# relays.net
KiCad netlist of a schematic drawn in Altium Designer
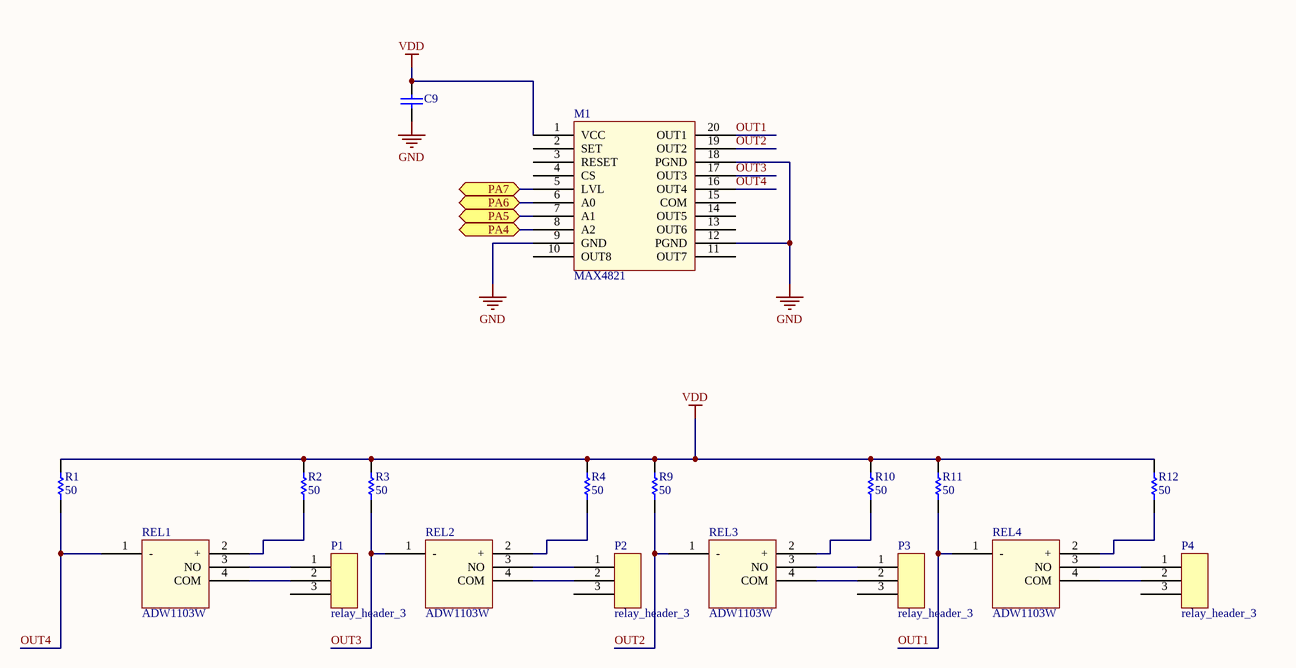
[diagram p0: relays.SchDoc]

(export (version "E")
  (design (tool "Eeschema 10.0.6"))
  (components
    (comp (ref "C9")
      (value "Cap Semi")
      (footprint "1608[0603]")
      (description "Capacitor (Semiconductor SIM Model)")
      (fields (field (name "MANUFACTURER") "TDK") (field (name "PUBLISHER") "Altium Limited"))
      (libsource (lib "Miscellaneous Devices") (part "Cap Semi"))
    )
    (comp (ref "M1")
      (value "MAX4821")
      (footprint "MAX4821")
      (fields (field (name "MANUFACTURER") "Maxim Integrated"))
      (libsource (lib "seeds") (part "MAX4821"))
    )
    (comp (ref "P1")
      (value "relay_header_3")
      (footprint "ac_header_3")
      (fields (field (name "MANUFACTURER") "On Shore Technology"))
      (libsource (lib "seeds") (part "relay_header_3"))
    )
    (comp (ref "P2")
      (value "relay_header_3")
      (footprint "ac_header_3")
      (fields (field (name "MANUFACTURER") "On Shore Technology"))
      (libsource (lib "seeds") (part "relay_header_3"))
    )
    (comp (ref "P3")
      (value "relay_header_3")
      (footprint "ac_header_3")
      (fields (field (name "MANUFACTURER") "On Shore Technology"))
      (libsource (lib "seeds") (part "relay_header_3"))
    )
    (comp (ref "P4")
      (value "relay_header_3")
      (footprint "ac_header_3")
      (fields (field (name "MANUFACTURER") "On Shore Technology"))
      (libsource (lib "seeds") (part "relay_header_3"))
    )
    (comp (ref "R1")
      (value "50")
      (footprint "0603R")
      (description "Resistor")
      (fields (field (name "MANUFACTURER") "Vishay Dale") (field (name "PUBLISHER") "Altium Limited"))
      (libsource (lib "MB1136") (part "Res1"))
    )
    (comp (ref "R2")
      (value "50")
      (footprint "0603R")
      (description "Resistor")
      (fields (field (name "MANUFACTURER") "Vishay Dale") (field (name "PUBLISHER") "Altium Limited"))
      (libsource (lib "MB1136") (part "Res1"))
    )
    (comp (ref "R3")
      (value "50")
      (footprint "0603R")
      (description "Resistor")
      (fields (field (name "MANUFACTURER") "Vishay Dale") (field (name "PUBLISHER") "Altium Limited"))
      (libsource (lib "MB1136") (part "Res1"))
    )
    (comp (ref "R4")
      (value "50")
      (footprint "0603R")
      (description "Resistor")
      (fields (field (name "MANUFACTURER") "Vishay Dale") (field (name "PUBLISHER") "Altium Limited"))
      (libsource (lib "MB1136") (part "Res1"))
    )
    (comp (ref "R9")
      (value "50")
      (footprint "0603R")
      (description "Resistor")
      (fields (field (name "MANUFACTURER") "Vishay Dale") (field (name "PUBLISHER") "Altium Limited"))
      (libsource (lib "MB1136") (part "Res1"))
    )
    (comp (ref "R10")
      (value "50")
      (footprint "0603R")
      (description "Resistor")
      (fields (field (name "MANUFACTURER") "Vishay Dale") (field (name "PUBLISHER") "Altium Limited"))
      (libsource (lib "MB1136") (part "Res1"))
    )
    (comp (ref "R11")
      (value "50")
      (footprint "0603R")
      (description "Resistor")
      (fields (field (name "MANUFACTURER") "Vishay Dale") (field (name "PUBLISHER") "Altium Limited"))
      (libsource (lib "MB1136") (part "Res1"))
    )
    (comp (ref "R12")
      (value "50")
      (footprint "0603R")
      (description "Resistor")
      (fields (field (name "MANUFACTURER") "Vishay Dale") (field (name "PUBLISHER") "Altium Limited"))
      (libsource (lib "MB1136") (part "Res1"))
    )
    (comp (ref "REL1")
      (value "ADW1103W")
      (footprint "ADW1103W")
      (fields (field (name "MANUFACTURER") "Panasonic"))
      (libsource (lib "seeds") (part "ADW1103W"))
    )
    (comp (ref "REL2")
      (value "ADW1103W")
      (footprint "ADW1103W")
      (fields (field (name "MANUFACTURER") "Panasonic"))
      (libsource (lib "seeds") (part "ADW1103W"))
    )
    (comp (ref "REL3")
      (value "ADW1103W")
      (footprint "ADW1103W")
      (fields (field (name "MANUFACTURER") "Panasonic"))
      (libsource (lib "seeds") (part "ADW1103W"))
    )
    (comp (ref "REL4")
      (value "ADW1103W")
      (footprint "ADW1103W")
      (fields (field (name "MANUFACTURER") "Panasonic"))
      (libsource (lib "seeds") (part "ADW1103W"))
    )
  )
  (nets
    (net (code "1") (name "/OUT1") (class "Default")
      (node (ref "M1") (pin "20") (pinfunction "OUT1_20") (pintype "passive"))
      (node (ref "R11") (pin "2") (pinfunction "2_2") (pintype "passive"))
      (node (ref "REL4") (pin "1") (pinfunction "-_1") (pintype "passive"))
    )
    (net (code "2") (name "/OUT2") (class "Default")
      (node (ref "M1") (pin "19") (pinfunction "OUT2_19") (pintype "passive"))
      (node (ref "R9") (pin "2") (pinfunction "2_2") (pintype "passive"))
      (node (ref "REL3") (pin "1") (pinfunction "-_1") (pintype "passive"))
    )
    (net (code "3") (name "/OUT3") (class "Default")
      (node (ref "M1") (pin "17") (pinfunction "OUT3_17") (pintype "passive"))
      (node (ref "R3") (pin "2") (pinfunction "2_2") (pintype "passive"))
      (node (ref "REL2") (pin "1") (pinfunction "-_1") (pintype "passive"))
    )
    (net (code "4") (name "/OUT4") (class "Default")
      (node (ref "M1") (pin "16") (pinfunction "OUT4_16") (pintype "passive"))
      (node (ref "R1") (pin "2") (pinfunction "2_2") (pintype "passive"))
      (node (ref "REL1") (pin "1") (pinfunction "-_1") (pintype "passive"))
    )
    (net (code "5") (name "/PA4") (class "Default")
      (node (ref "M1") (pin "8") (pinfunction "A2_8") (pintype "passive"))
    )
    (net (code "6") (name "/PA5") (class "Default")
      (node (ref "M1") (pin "7") (pinfunction "A1_7") (pintype "passive"))
    )
    (net (code "7") (name "/PA6") (class "Default")
      (node (ref "M1") (pin "6") (pinfunction "A0_6") (pintype "passive"))
    )
    (net (code "8") (name "/PA7") (class "Default")
      (node (ref "M1") (pin "5") (pinfunction "LVL_5") (pintype "passive"))
    )
    (net (code "9") (name "GND") (class "Default")
      (node (ref "C9") (pin "2") (pinfunction "2_2") (pintype "passive"))
      (node (ref "M1") (pin "12") (pinfunction "PGND_12") (pintype "passive"))
      (node (ref "M1") (pin "18") (pinfunction "PGND_18") (pintype "passive"))
      (node (ref "M1") (pin "9") (pinfunction "GND_9") (pintype "passive"))
    )
    (net (code "10") (name "Net-(REL1-+)") (class "Default")
      (node (ref "R2") (pin "2") (pinfunction "2_2") (pintype "passive"))
      (node (ref "REL1") (pin "2") (pinfunction "+_2") (pintype "passive"))
    )
    (net (code "11") (name "Net-(REL1-COM)") (class "Default")
      (node (ref "P1") (pin "2") (pintype "power_in"))
      (node (ref "REL1") (pin "4") (pinfunction "COM_4") (pintype "passive"))
    )
    (net (code "12") (name "Net-(REL1-NO)") (class "Default")
      (node (ref "P1") (pin "1") (pintype "power_in"))
      (node (ref "REL1") (pin "3") (pinfunction "NO_3") (pintype "passive"))
    )
    (net (code "13") (name "Net-(REL2-+)") (class "Default")
      (node (ref "R4") (pin "2") (pinfunction "2_2") (pintype "passive"))
      (node (ref "REL2") (pin "2") (pinfunction "+_2") (pintype "passive"))
    )
    (net (code "14") (name "Net-(REL2-COM)") (class "Default")
      (node (ref "P2") (pin "2") (pintype "power_in"))
      (node (ref "REL2") (pin "4") (pinfunction "COM_4") (pintype "passive"))
    )
    (net (code "15") (name "Net-(REL2-NO)") (class "Default")
      (node (ref "P2") (pin "1") (pintype "power_in"))
      (node (ref "REL2") (pin "3") (pinfunction "NO_3") (pintype "passive"))
    )
    (net (code "16") (name "Net-(REL3-+)") (class "Default")
      (node (ref "R10") (pin "2") (pinfunction "2_2") (pintype "passive"))
      (node (ref "REL3") (pin "2") (pinfunction "+_2") (pintype "passive"))
    )
    (net (code "17") (name "Net-(REL3-COM)") (class "Default")
      (node (ref "P3") (pin "2") (pintype "power_in"))
      (node (ref "REL3") (pin "4") (pinfunction "COM_4") (pintype "passive"))
    )
    (net (code "18") (name "Net-(REL3-NO)") (class "Default")
      (node (ref "P3") (pin "1") (pintype "power_in"))
      (node (ref "REL3") (pin "3") (pinfunction "NO_3") (pintype "passive"))
    )
    (net (code "19") (name "Net-(REL4-+)") (class "Default")
      (node (ref "R12") (pin "2") (pinfunction "2_2") (pintype "passive"))
      (node (ref "REL4") (pin "2") (pinfunction "+_2") (pintype "passive"))
    )
    (net (code "20") (name "Net-(REL4-COM)") (class "Default")
      (node (ref "P4") (pin "2") (pintype "power_in"))
      (node (ref "REL4") (pin "4") (pinfunction "COM_4") (pintype "passive"))
    )
    (net (code "21") (name "Net-(REL4-NO)") (class "Default")
      (node (ref "P4") (pin "1") (pintype "power_in"))
      (node (ref "REL4") (pin "3") (pinfunction "NO_3") (pintype "passive"))
    )
    (net (code "22") (name "VDD") (class "Default")
      (node (ref "C9") (pin "1") (pinfunction "1_1") (pintype "passive"))
      (node (ref "M1") (pin "1") (pinfunction "VCC_1") (pintype "passive"))
      (node (ref "R1") (pin "1") (pinfunction "1_1") (pintype "passive"))
      (node (ref "R10") (pin "1") (pinfunction "1_1") (pintype "passive"))
      (node (ref "R11") (pin "1") (pinfunction "1_1") (pintype "passive"))
      (node (ref "R12") (pin "1") (pinfunction "1_1") (pintype "passive"))
      (node (ref "R2") (pin "1") (pinfunction "1_1") (pintype "passive"))
      (node (ref "R3") (pin "1") (pinfunction "1_1") (pintype "passive"))
      (node (ref "R4") (pin "1") (pinfunction "1_1") (pintype "passive"))
      (node (ref "R9") (pin "1") (pinfunction "1_1") (pintype "passive"))
    )
    (net (code "23") (name "unconnected-(M1-COM-Pad15)") (class "Default")
      (node (ref "M1") (pin "15") (pinfunction "COM_15") (pintype "passive"))
    )
    (net (code "24") (name "unconnected-(M1-CS-Pad4)") (class "Default")
      (node (ref "M1") (pin "4") (pinfunction "CS_4") (pintype "passive"))
    )
    (net (code "25") (name "unconnected-(M1-OUT5-Pad14)") (class "Default")
      (node (ref "M1") (pin "14") (pinfunction "OUT5_14") (pintype "passive"))
    )
    (net (code "26") (name "unconnected-(M1-OUT6-Pad13)") (class "Default")
      (node (ref "M1") (pin "13") (pinfunction "OUT6_13") (pintype "passive"))
    )
    (net (code "27") (name "unconnected-(M1-OUT7-Pad11)") (class "Default")
      (node (ref "M1") (pin "11") (pinfunction "OUT7_11") (pintype "passive"))
    )
    (net (code "28") (name "unconnected-(M1-OUT8-Pad10)") (class "Default")
      (node (ref "M1") (pin "10") (pinfunction "OUT8_10") (pintype "passive"))
    )
    (net (code "29") (name "unconnected-(M1-RESET-Pad3)") (class "Default")
      (node (ref "M1") (pin "3") (pinfunction "RESET_3") (pintype "passive"))
    )
    (net (code "30") (name "unconnected-(M1-SET-Pad2)") (class "Default")
      (node (ref "M1") (pin "2") (pinfunction "SET_2") (pintype "passive"))
    )
    (net (code "31") (name "unconnected-(P1-Pad3)") (class "Default")
      (node (ref "P1") (pin "3") (pintype "power_in"))
    )
    (net (code "32") (name "unconnected-(P2-Pad3)") (class "Default")
      (node (ref "P2") (pin "3") (pintype "power_in"))
    )
    (net (code "33") (name "unconnected-(P3-Pad3)") (class "Default")
      (node (ref "P3") (pin "3") (pintype "power_in"))
    )
    (net (code "34") (name "unconnected-(P4-Pad3)") (class "Default")
      (node (ref "P4") (pin "3") (pintype "power_in"))
    )
  )
)
